# SIRA.net
KiCad netlist of a schematic drawn in Altium Designer
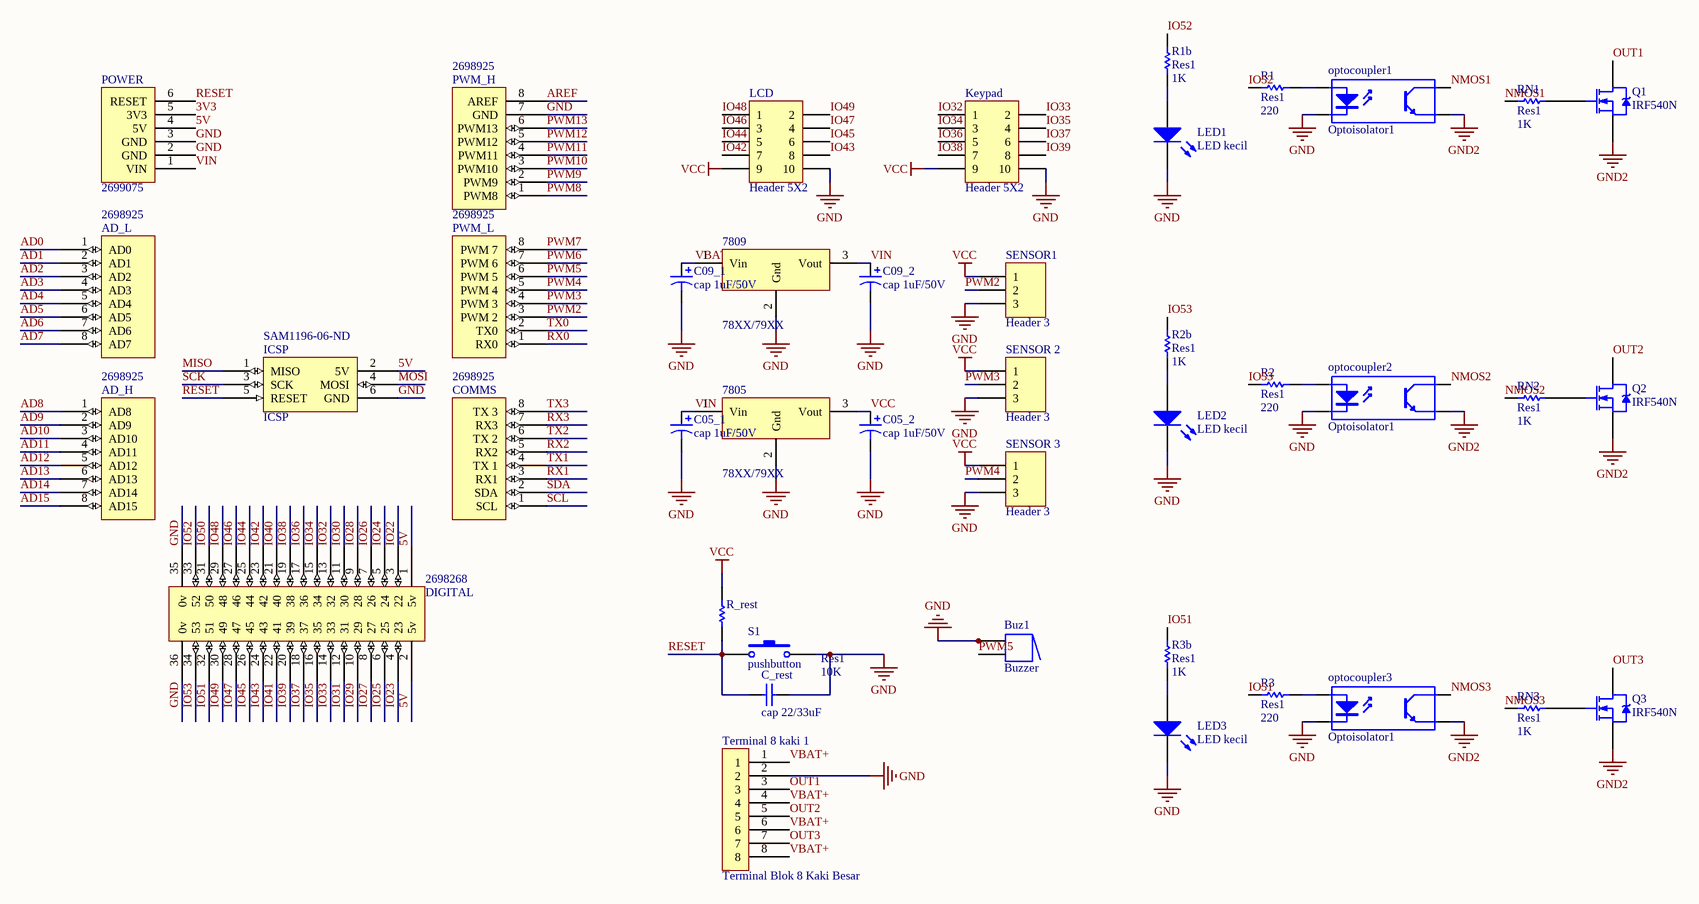
[diagram p0: SIRA.SchDoc]

(export (version "E")
  (design (tool "Eeschema 10.0.6"))
  (components
    (comp (ref "7805")
      (value "78XX/79XX")
      (footprint "78XX/79XX diri")
      (libsource (lib "agfa other components") (part "7805/7809/7812/7905/7909/7912"))
    )
    (comp (ref "7809")
      (value "78XX/79XX")
      (footprint "78XX/79XX diri")
      (libsource (lib "agfa other components") (part "7805/7809/7812/7905/7909/7912"))
    )
    (comp (ref "AD_H")
      (value "AD_H")
      (footprint "Header 8x1 8.5mm")
      (fields (field (name "SUPPLIER PART NUMBER 4") "2698925"))
      (libsource (lib "Header") (part "AD_H"))
    )
    (comp (ref "AD_L")
      (value "AD_L")
      (footprint "Header 8x1 8.5mm")
      (fields (field (name "SUPPLIER PART NUMBER 5") "2698925"))
      (libsource (lib "Header") (part "AD_L"))
    )
    (comp (ref "Buz1")
      (value "Buzzer")
      (footprint "ABSM-1574")
      (description "Magnetic Transducer Buzzer")
      (fields (field (name "PUBLISHER") "Altium Limited"))
      (libsource (lib "Miscellaneous Devices") (part "Buzzer"))
    )
    (comp (ref "C05_1")
      (value "cap 1uF/50V")
      (footprint "cap 1uF/50V")
      (libsource (lib "agfa other components") (part "cap 1uF/50V"))
    )
    (comp (ref "C05_2")
      (value "cap 1uF/50V")
      (footprint "cap 1uF/50V")
      (libsource (lib "agfa other components") (part "cap 1uF/50V"))
    )
    (comp (ref "C09_1")
      (value "cap 1uF/50V")
      (footprint "cap 1uF/50V")
      (libsource (lib "agfa other components") (part "cap 1uF/50V"))
    )
    (comp (ref "C09_2")
      (value "cap 1uF/50V")
      (footprint "cap 1uF/50V")
      (libsource (lib "agfa other components") (part "cap 1uF/50V"))
    )
    (comp (ref "COMMS")
      (value "Communication")
      (footprint "Header 8x1 8.5mm")
      (fields (field (name "SUPPLIER PART NUMBER 4") "2698925"))
      (libsource (lib "Header") (part "Communication"))
    )
    (comp (ref "C_rest")
      (value "cap 22/33uF")
      (footprint "cap 22/33uF")
      (libsource (lib "agfa other components") (part "cap 22/33uF"))
    )
    (comp (ref "DIGITAL")
      (value "IO_36")
      (footprint "HEADER 36X 8MM")
      (fields (field (name "SUPPLIER PART NUMBER 5") "2698268"))
      (libsource (lib "Header") (part "IO_36"))
    )
    (comp (ref "ICSP")
      (value "ICSP")
      (footprint "ICSP")
      (fields (field (name "SUPPLIER PART NUMBER 5") "SAM1196-06-ND"))
      (libsource (lib "Header") (part "ICSP"))
    )
    (comp (ref "Keypad")
      (value "Header 5X2")
      (footprint "HDR2X5")
      (description "Header, 5-Pin, Dual row")
      (fields (field (name "PUBLISHER") "Altium Limited"))
      (libsource (lib "Miscellaneous Connectors") (part "Header 5X2"))
    )
    (comp (ref "LCD")
      (value "Header 5X2")
      (footprint "HDR2X5")
      (description "Header, 5-Pin, Dual row")
      (fields (field (name "PUBLISHER") "Altium Limited"))
      (libsource (lib "Miscellaneous Connectors") (part "Header 5X2"))
    )
    (comp (ref "LED1")
      (value "LED kecil")
      (footprint "LED kecil")
      (libsource (lib "agfa other components") (part "LED kecil"))
    )
    (comp (ref "LED2")
      (value "LED kecil")
      (footprint "LED kecil")
      (libsource (lib "agfa other components") (part "LED kecil"))
    )
    (comp (ref "LED3")
      (value "LED kecil")
      (footprint "LED kecil")
      (libsource (lib "agfa other components") (part "LED kecil"))
    )
    (comp (ref "optocoupler1")
      (value "Optoisolator1")
      (footprint "DIP-4")
      (description "4-Pin Phototransistor Optocoupler")
      (fields (field (name "PUBLISHER") "Altium Limited"))
      (libsource (lib "Miscellaneous Devices") (part "Optoisolator1"))
    )
    (comp (ref "optocoupler2")
      (value "Optoisolator1")
      (footprint "DIP-4")
      (description "4-Pin Phototransistor Optocoupler")
      (fields (field (name "PUBLISHER") "Altium Limited"))
      (libsource (lib "Miscellaneous Devices") (part "Optoisolator1"))
    )
    (comp (ref "optocoupler3")
      (value "Optoisolator1")
      (footprint "DIP-4")
      (description "4-Pin Phototransistor Optocoupler")
      (fields (field (name "PUBLISHER") "Altium Limited"))
      (libsource (lib "Miscellaneous Devices") (part "Optoisolator1"))
    )
    (comp (ref "POWER")
      (value "POWER")
      (footprint "Header 6x1 8.5mm")
      (fields (field (name "SUPPLIER PART NUMBER 2") "2699075"))
      (libsource (lib "Header") (part "POWER"))
    )
    (comp (ref "PWM_H")
      (value "PWM_H")
      (footprint "Header 8x1 8.5mm")
      (fields (field (name "SUPPLIER PART NUMBER 4") "2698925"))
      (libsource (lib "Header") (part "PWM_H"))
    )
    (comp (ref "PWM_L")
      (value "PWM_L")
      (footprint "Header 8x1 8.5mm")
      (fields (field (name "SUPPLIER PART NUMBER 4") "2698925"))
      (libsource (lib "Header") (part "PWM_L"))
    )
    (comp (ref "Q1")
      (value "IRF540N")
      (footprint "TO-220AB")
      (description "HEXFET Power MOSFET")
      (fields (field (name "PUBLISHER") "Altium Limited"))
      (libsource (lib "IR Discrete MOSFET - Power") (part "IRF540N"))
    )
    (comp (ref "Q2")
      (value "IRF540N")
      (footprint "TO-220AB")
      (description "HEXFET Power MOSFET")
      (fields (field (name "PUBLISHER") "Altium Limited"))
      (libsource (lib "IR Discrete MOSFET - Power") (part "IRF540N"))
    )
    (comp (ref "Q3")
      (value "IRF540N")
      (footprint "TO-220AB")
      (description "HEXFET Power MOSFET")
      (fields (field (name "PUBLISHER") "Altium Limited"))
      (libsource (lib "IR Discrete MOSFET - Power") (part "IRF540N"))
    )
    (comp (ref "R1")
      (value "Res1")
      (footprint "AXIAL-0.3")
      (description "Resistor")
      (fields (field (name "ALTIUM_VALUE") "220") (field (name "PUBLISHER") "Altium Limited"))
      (libsource (lib "Miscellaneous Devices") (part "Res1"))
    )
    (comp (ref "R1b")
      (value "Res1")
      (footprint "AXIAL-0.3")
      (description "Resistor")
      (fields (field (name "ALTIUM_VALUE") "1K") (field (name "PUBLISHER") "Altium Limited"))
      (libsource (lib "Miscellaneous Devices") (part "Res1"))
    )
    (comp (ref "R2")
      (value "Res1")
      (footprint "AXIAL-0.3")
      (description "Resistor")
      (fields (field (name "ALTIUM_VALUE") "220") (field (name "PUBLISHER") "Altium Limited"))
      (libsource (lib "Miscellaneous Devices") (part "Res1"))
    )
    (comp (ref "R2b")
      (value "Res1")
      (footprint "AXIAL-0.3")
      (description "Resistor")
      (fields (field (name "ALTIUM_VALUE") "1K") (field (name "PUBLISHER") "Altium Limited"))
      (libsource (lib "Miscellaneous Devices") (part "Res1"))
    )
    (comp (ref "R3")
      (value "Res1")
      (footprint "AXIAL-0.3")
      (description "Resistor")
      (fields (field (name "ALTIUM_VALUE") "220") (field (name "PUBLISHER") "Altium Limited"))
      (libsource (lib "Miscellaneous Devices") (part "Res1"))
    )
    (comp (ref "R3b")
      (value "Res1")
      (footprint "AXIAL-0.3")
      (description "Resistor")
      (fields (field (name "ALTIUM_VALUE") "1K") (field (name "PUBLISHER") "Altium Limited"))
      (libsource (lib "Miscellaneous Devices") (part "Res1"))
    )
    (comp (ref "RN1")
      (value "Res1")
      (footprint "AXIAL-0.3")
      (description "Resistor")
      (fields (field (name "ALTIUM_VALUE") "1K") (field (name "PUBLISHER") "Altium Limited"))
      (libsource (lib "Miscellaneous Devices") (part "Res1"))
    )
    (comp (ref "RN2")
      (value "Res1")
      (footprint "AXIAL-0.3")
      (description "Resistor")
      (fields (field (name "ALTIUM_VALUE") "1K") (field (name "PUBLISHER") "Altium Limited"))
      (libsource (lib "Miscellaneous Devices") (part "Res1"))
    )
    (comp (ref "RN3")
      (value "Res1")
      (footprint "AXIAL-0.3")
      (description "Resistor")
      (fields (field (name "ALTIUM_VALUE") "1K") (field (name "PUBLISHER") "Altium Limited"))
      (libsource (lib "Miscellaneous Devices") (part "Res1"))
    )
    (comp (ref "R_rest")
      (value "Res1")
      (footprint "AXIAL-0.3")
      (description "Resistor")
      (fields (field (name "ALTIUM_VALUE") "10K") (field (name "PUBLISHER") "Altium Limited"))
      (libsource (lib "Miscellaneous Devices") (part "Res1"))
    )
    (comp (ref "S1")
      (value "pushbutton")
      (footprint "pushbutton")
      (libsource (lib "agfa other components") (part "pushbutton"))
    )
    (comp (ref "SENSOR 2")
      (value "Header 3")
      (footprint "HDR1X3")
      (description "Header, 3-Pin")
      (fields (field (name "PUBLISHER") "Altium Limited"))
      (libsource (lib "Miscellaneous Connectors") (part "Header 3"))
    )
    (comp (ref "SENSOR 3")
      (value "Header 3")
      (footprint "HDR1X3")
      (description "Header, 3-Pin")
      (fields (field (name "PUBLISHER") "Altium Limited"))
      (libsource (lib "Miscellaneous Connectors") (part "Header 3"))
    )
    (comp (ref "SENSOR1")
      (value "Header 3")
      (footprint "HDR1X3")
      (description "Header, 3-Pin")
      (fields (field (name "PUBLISHER") "Altium Limited"))
      (libsource (lib "Miscellaneous Connectors") (part "Header 3"))
    )
    (comp (ref "Terminal 8 kaki 1")
      (value "Terminal Blok 8 Kaki Besar")
      (footprint "TERMINAL 8 KAKI")
      (libsource (lib "Library Ausiher") (part "Terminal Block 8 kaki"))
    )
  )
  (nets
    (net (code "1") (name "/3V3") (class "Default")
      (node (ref "POWER") (pin "5") (pinfunction "3V3_5") (pintype "power_in"))
    )
    (net (code "2") (name "/5V") (class "Default")
      (node (ref "DIGITAL") (pin "1") (pinfunction "5v_1") (pintype "power_in"))
      (node (ref "DIGITAL") (pin "2") (pinfunction "5v_2") (pintype "power_in"))
      (node (ref "ICSP") (pin "2") (pinfunction "5V_2") (pintype "power_in"))
      (node (ref "POWER") (pin "4") (pinfunction "5V_4") (pintype "power_in"))
    )
    (net (code "3") (name "/AD0") (class "Default")
      (node (ref "AD_L") (pin "1") (pinfunction "AD0_1") (pintype "bidirectional"))
    )
    (net (code "4") (name "/AD1") (class "Default")
      (node (ref "AD_L") (pin "2") (pinfunction "AD1_2") (pintype "bidirectional"))
    )
    (net (code "5") (name "/AD2") (class "Default")
      (node (ref "AD_L") (pin "3") (pinfunction "AD2_3") (pintype "bidirectional"))
    )
    (net (code "6") (name "/AD3") (class "Default")
      (node (ref "AD_L") (pin "4") (pinfunction "AD3_4") (pintype "bidirectional"))
    )
    (net (code "7") (name "/AD4") (class "Default")
      (node (ref "AD_L") (pin "5") (pinfunction "AD4_5") (pintype "bidirectional"))
    )
    (net (code "8") (name "/AD5") (class "Default")
      (node (ref "AD_L") (pin "6") (pinfunction "AD5_6") (pintype "bidirectional"))
    )
    (net (code "9") (name "/AD6") (class "Default")
      (node (ref "AD_L") (pin "7") (pinfunction "AD6_7") (pintype "bidirectional"))
    )
    (net (code "10") (name "/AD7") (class "Default")
      (node (ref "AD_L") (pin "8") (pinfunction "AD7_8") (pintype "bidirectional"))
    )
    (net (code "11") (name "/AD8") (class "Default")
      (node (ref "AD_H") (pin "1") (pinfunction "AD8_1") (pintype "bidirectional"))
    )
    (net (code "12") (name "/AD9") (class "Default")
      (node (ref "AD_H") (pin "2") (pinfunction "AD9_2") (pintype "bidirectional"))
    )
    (net (code "13") (name "/AD10") (class "Default")
      (node (ref "AD_H") (pin "3") (pinfunction "AD10_3") (pintype "bidirectional"))
    )
    (net (code "14") (name "/AD11") (class "Default")
      (node (ref "AD_H") (pin "4") (pinfunction "AD11_4") (pintype "bidirectional"))
    )
    (net (code "15") (name "/AD12") (class "Default")
      (node (ref "AD_H") (pin "5") (pinfunction "AD12_5") (pintype "bidirectional"))
    )
    (net (code "16") (name "/AD13") (class "Default")
      (node (ref "AD_H") (pin "6") (pinfunction "AD13_6") (pintype "bidirectional"))
    )
    (net (code "17") (name "/AD14") (class "Default")
      (node (ref "AD_H") (pin "7") (pinfunction "AD14_7") (pintype "bidirectional"))
    )
    (net (code "18") (name "/AD15") (class "Default")
      (node (ref "AD_H") (pin "8") (pinfunction "AD15_8") (pintype "bidirectional"))
    )
    (net (code "19") (name "/AREF") (class "Default")
      (node (ref "PWM_H") (pin "8") (pinfunction "AREF_8") (pintype "passive"))
    )
    (net (code "20") (name "/IO22") (class "Default")
      (node (ref "DIGITAL") (pin "3") (pinfunction "22_3") (pintype "bidirectional"))
    )
    (net (code "21") (name "/IO23") (class "Default")
      (node (ref "DIGITAL") (pin "4") (pinfunction "23_4") (pintype "bidirectional"))
    )
    (net (code "22") (name "/IO24") (class "Default")
      (node (ref "DIGITAL") (pin "5") (pinfunction "24_5") (pintype "bidirectional"))
    )
    (net (code "23") (name "/IO25") (class "Default")
      (node (ref "DIGITAL") (pin "6") (pinfunction "25_6") (pintype "bidirectional"))
    )
    (net (code "24") (name "/IO26") (class "Default")
      (node (ref "DIGITAL") (pin "7") (pinfunction "26_7") (pintype "bidirectional"))
    )
    (net (code "25") (name "/IO27") (class "Default")
      (node (ref "DIGITAL") (pin "8") (pinfunction "27_8") (pintype "bidirectional"))
    )
    (net (code "26") (name "/IO28") (class "Default")
      (node (ref "DIGITAL") (pin "9") (pinfunction "28_9") (pintype "bidirectional"))
    )
    (net (code "27") (name "/IO29") (class "Default")
      (node (ref "DIGITAL") (pin "10") (pinfunction "29_10") (pintype "bidirectional"))
    )
    (net (code "28") (name "/IO30") (class "Default")
      (node (ref "DIGITAL") (pin "11") (pinfunction "30_11") (pintype "bidirectional"))
    )
    (net (code "29") (name "/IO31") (class "Default")
      (node (ref "DIGITAL") (pin "12") (pinfunction "31_12") (pintype "bidirectional"))
    )
    (net (code "30") (name "/IO32") (class "Default")
      (node (ref "DIGITAL") (pin "13") (pinfunction "32_13") (pintype "bidirectional"))
      (node (ref "Keypad") (pin "1") (pinfunction "1_1") (pintype "passive"))
    )
    (net (code "31") (name "/IO33") (class "Default")
      (node (ref "DIGITAL") (pin "14") (pinfunction "33_14") (pintype "bidirectional"))
      (node (ref "Keypad") (pin "2") (pinfunction "2_2") (pintype "passive"))
    )
    (net (code "32") (name "/IO34") (class "Default")
      (node (ref "DIGITAL") (pin "15") (pinfunction "34_15") (pintype "bidirectional"))
      (node (ref "Keypad") (pin "3") (pinfunction "3_3") (pintype "passive"))
    )
    (net (code "33") (name "/IO35") (class "Default")
      (node (ref "DIGITAL") (pin "16") (pinfunction "35_16") (pintype "bidirectional"))
      (node (ref "Keypad") (pin "4") (pinfunction "4_4") (pintype "passive"))
    )
    (net (code "34") (name "/IO36") (class "Default")
      (node (ref "DIGITAL") (pin "17") (pinfunction "36_17") (pintype "bidirectional"))
      (node (ref "Keypad") (pin "5") (pinfunction "5_5") (pintype "passive"))
    )
    (net (code "35") (name "/IO37") (class "Default")
      (node (ref "DIGITAL") (pin "18") (pinfunction "37_18") (pintype "bidirectional"))
      (node (ref "Keypad") (pin "6") (pinfunction "6_6") (pintype "passive"))
    )
    (net (code "36") (name "/IO38") (class "Default")
      (node (ref "DIGITAL") (pin "19") (pinfunction "38_19") (pintype "bidirectional"))
      (node (ref "Keypad") (pin "7") (pinfunction "7_7") (pintype "passive"))
    )
    (net (code "37") (name "/IO39") (class "Default")
      (node (ref "DIGITAL") (pin "20") (pinfunction "39_20") (pintype "bidirectional"))
      (node (ref "Keypad") (pin "8") (pinfunction "8_8") (pintype "passive"))
    )
    (net (code "38") (name "/IO40") (class "Default")
      (node (ref "DIGITAL") (pin "21") (pinfunction "40_21") (pintype "bidirectional"))
    )
    (net (code "39") (name "/IO41") (class "Default")
      (node (ref "DIGITAL") (pin "22") (pinfunction "41_22") (pintype "bidirectional"))
    )
    (net (code "40") (name "/IO42") (class "Default")
      (node (ref "DIGITAL") (pin "23") (pinfunction "42_23") (pintype "bidirectional"))
      (node (ref "LCD") (pin "7") (pinfunction "7_7") (pintype "passive"))
    )
    (net (code "41") (name "/IO43") (class "Default")
      (node (ref "DIGITAL") (pin "24") (pinfunction "43_24") (pintype "bidirectional"))
      (node (ref "LCD") (pin "8") (pinfunction "8_8") (pintype "passive"))
    )
    (net (code "42") (name "/IO44") (class "Default")
      (node (ref "DIGITAL") (pin "25") (pinfunction "44_25") (pintype "bidirectional"))
      (node (ref "LCD") (pin "5") (pinfunction "5_5") (pintype "passive"))
    )
    (net (code "43") (name "/IO45") (class "Default")
      (node (ref "DIGITAL") (pin "26") (pinfunction "45_26") (pintype "bidirectional"))
      (node (ref "LCD") (pin "6") (pinfunction "6_6") (pintype "passive"))
    )
    (net (code "44") (name "/IO46") (class "Default")
      (node (ref "DIGITAL") (pin "27") (pinfunction "46_27") (pintype "bidirectional"))
      (node (ref "LCD") (pin "3") (pinfunction "3_3") (pintype "passive"))
    )
    (net (code "45") (name "/IO47") (class "Default")
      (node (ref "DIGITAL") (pin "28") (pinfunction "47_28") (pintype "bidirectional"))
      (node (ref "LCD") (pin "4") (pinfunction "4_4") (pintype "passive"))
    )
    (net (code "46") (name "/IO48") (class "Default")
      (node (ref "DIGITAL") (pin "29") (pinfunction "48_29") (pintype "bidirectional"))
      (node (ref "LCD") (pin "1") (pinfunction "1_1") (pintype "passive"))
    )
    (net (code "47") (name "/IO49") (class "Default")
      (node (ref "DIGITAL") (pin "30") (pinfunction "49_30") (pintype "bidirectional"))
      (node (ref "LCD") (pin "2") (pinfunction "2_2") (pintype "passive"))
    )
    (net (code "48") (name "/IO50") (class "Default")
      (node (ref "DIGITAL") (pin "31") (pinfunction "50_31") (pintype "bidirectional"))
    )
    (net (code "49") (name "/IO51") (class "Default")
      (node (ref "DIGITAL") (pin "32") (pinfunction "51_32") (pintype "bidirectional"))
      (node (ref "R3") (pin "1") (pinfunction "1_1") (pintype "passive"))
      (node (ref "R3b") (pin "2") (pinfunction "2_2") (pintype "passive"))
    )
    (net (code "50") (name "/IO52") (class "Default")
      (node (ref "DIGITAL") (pin "33") (pinfunction "52_33") (pintype "bidirectional"))
      (node (ref "R1") (pin "1") (pinfunction "1_1") (pintype "passive"))
      (node (ref "R1b") (pin "2") (pinfunction "2_2") (pintype "passive"))
    )
    (net (code "51") (name "/IO53") (class "Default")
      (node (ref "DIGITAL") (pin "34") (pinfunction "53_34") (pintype "bidirectional"))
      (node (ref "R2") (pin "1") (pinfunction "1_1") (pintype "passive"))
      (node (ref "R2b") (pin "2") (pinfunction "2_2") (pintype "passive"))
    )
    (net (code "52") (name "/MISO") (class "Default")
      (node (ref "ICSP") (pin "1") (pinfunction "MISO_1") (pintype "bidirectional"))
    )
    (net (code "53") (name "/MOSI") (class "Default")
      (node (ref "ICSP") (pin "4") (pinfunction "MOSI_4") (pintype "bidirectional"))
    )
    (net (code "54") (name "/NMOS1") (class "Default")
      (node (ref "RN1") (pin "1") (pinfunction "1_1") (pintype "passive"))
      (node (ref "optocoupler1") (pin "4") (pinfunction "C_4") (pintype "passive"))
    )
    (net (code "55") (name "/NMOS2") (class "Default")
      (node (ref "RN2") (pin "1") (pinfunction "1_1") (pintype "passive"))
      (node (ref "optocoupler2") (pin "4") (pinfunction "C_4") (pintype "passive"))
    )
    (net (code "56") (name "/NMOS3") (class "Default")
      (node (ref "RN3") (pin "1") (pinfunction "1_1") (pintype "passive"))
      (node (ref "optocoupler3") (pin "4") (pinfunction "C_4") (pintype "passive"))
    )
    (net (code "57") (name "/OUT1") (class "Default")
      (node (ref "Q1") (pin "2") (pinfunction "D_2") (pintype "passive"))
      (node (ref "Terminal 8 kaki 1") (pin "3") (pinfunction "3_3") (pintype "passive"))
    )
    (net (code "58") (name "/OUT2") (class "Default")
      (node (ref "Q2") (pin "2") (pinfunction "D_2") (pintype "passive"))
      (node (ref "Terminal 8 kaki 1") (pin "5") (pinfunction "5_5") (pintype "passive"))
    )
    (net (code "59") (name "/OUT3") (class "Default")
      (node (ref "Q3") (pin "2") (pinfunction "D_2") (pintype "passive"))
      (node (ref "Terminal 8 kaki 1") (pin "7") (pinfunction "7_7") (pintype "passive"))
    )
    (net (code "60") (name "/PWM2") (class "Default")
      (node (ref "PWM_L") (pin "3") (pinfunction "PWM_2_3") (pintype "bidirectional"))
      (node (ref "SENSOR1") (pin "2") (pinfunction "2_2") (pintype "passive"))
    )
    (net (code "61") (name "/PWM3") (class "Default")
      (node (ref "PWM_L") (pin "4") (pinfunction "PWM_3_4") (pintype "bidirectional"))
      (node (ref "SENSOR 2") (pin "2") (pinfunction "2_2") (pintype "passive"))
    )
    (net (code "62") (name "/PWM4") (class "Default")
      (node (ref "PWM_L") (pin "5") (pinfunction "PWM_4_5") (pintype "bidirectional"))
      (node (ref "SENSOR 3") (pin "2") (pinfunction "2_2") (pintype "passive"))
    )
    (net (code "63") (name "/PWM5") (class "Default")
      (node (ref "Buz1") (pin "2") (pinfunction "2_2") (pintype "passive"))
      (node (ref "Buz1") (pin "2A") (pinfunction "2A_2A") (pintype "passive"))
      (node (ref "PWM_L") (pin "6") (pinfunction "PWM_5_6") (pintype "bidirectional"))
    )
    (net (code "64") (name "/PWM6") (class "Default")
      (node (ref "PWM_L") (pin "7") (pinfunction "PWM_6_7") (pintype "bidirectional"))
    )
    (net (code "65") (name "/PWM7") (class "Default")
      (node (ref "PWM_L") (pin "8") (pinfunction "PWM_7_8") (pintype "bidirectional"))
    )
    (net (code "66") (name "/PWM8") (class "Default")
      (node (ref "PWM_H") (pin "1") (pinfunction "PWM8_1") (pintype "bidirectional"))
    )
    (net (code "67") (name "/PWM9") (class "Default")
      (node (ref "PWM_H") (pin "2") (pinfunction "PWM9_2") (pintype "bidirectional"))
    )
    (net (code "68") (name "/PWM10") (class "Default")
      (node (ref "PWM_H") (pin "3") (pinfunction "PWM10_3") (pintype "bidirectional"))
    )
    (net (code "69") (name "/PWM11") (class "Default")
      (node (ref "PWM_H") (pin "4") (pinfunction "PWM11_4") (pintype "bidirectional"))
    )
    (net (code "70") (name "/PWM12") (class "Default")
      (node (ref "PWM_H") (pin "5") (pinfunction "PWM12_5") (pintype "bidirectional"))
    )
    (net (code "71") (name "/PWM13") (class "Default")
      (node (ref "PWM_H") (pin "6") (pinfunction "PWM13_6") (pintype "bidirectional"))
    )
    (net (code "72") (name "/RESET") (class "Default")
      (node (ref "C_rest") (pin "2") (pinfunction "2_2") (pintype "passive"))
      (node (ref "ICSP") (pin "5") (pinfunction "RESET_5") (pintype "input"))
      (node (ref "POWER") (pin "6") (pinfunction "RESET_6") (pintype "passive"))
      (node (ref "R_rest") (pin "1") (pinfunction "1_1") (pintype "passive"))
      (node (ref "S1") (pin "1") (pinfunction "1_1") (pintype "passive"))
    )
    (net (code "73") (name "/RX0") (class "Default")
      (node (ref "PWM_L") (pin "1") (pinfunction "RX0_1") (pintype "bidirectional"))
    )
    (net (code "74") (name "/RX1") (class "Default")
      (node (ref "COMMS") (pin "3") (pinfunction "RX1_3") (pintype "bidirectional"))
    )
    (net (code "75") (name "/RX2") (class "Default")
      (node (ref "COMMS") (pin "5") (pinfunction "RX2_5") (pintype "bidirectional"))
    )
    (net (code "76") (name "/RX3") (class "Default")
      (node (ref "COMMS") (pin "7") (pinfunction "RX3_7") (pintype "bidirectional"))
    )
    (net (code "77") (name "/SCK") (class "Default")
      (node (ref "ICSP") (pin "3") (pinfunction "SCK_3") (pintype "bidirectional"))
    )
    (net (code "78") (name "/SCL") (class "Default")
      (node (ref "COMMS") (pin "1") (pinfunction "SCL_1") (pintype "bidirectional"))
    )
    (net (code "79") (name "/SDA") (class "Default")
      (node (ref "COMMS") (pin "2") (pinfunction "SDA_2") (pintype "bidirectional"))
    )
    (net (code "80") (name "/TX0") (class "Default")
      (node (ref "PWM_L") (pin "2") (pinfunction "TX0_2") (pintype "bidirectional"))
    )
    (net (code "81") (name "/TX1") (class "Default")
      (node (ref "COMMS") (pin "4") (pinfunction "TX_1_4") (pintype "bidirectional"))
    )
    (net (code "82") (name "/TX2") (class "Default")
      (node (ref "COMMS") (pin "6") (pinfunction "TX_2_6") (pintype "bidirectional"))
    )
    (net (code "83") (name "/TX3") (class "Default")
      (node (ref "COMMS") (pin "8") (pinfunction "TX_3_8") (pintype "bidirectional"))
    )
    (net (code "84") (name "/VBAT+") (class "Default")
      (node (ref "7809") (pin "1") (pinfunction "Vin_1") (pintype "passive"))
      (node (ref "C09_1") (pin "1") (pinfunction "1_1") (pintype "passive"))
      (node (ref "Terminal 8 kaki 1") (pin "1") (pinfunction "1_1") (pintype "passive"))
      (node (ref "Terminal 8 kaki 1") (pin "4") (pinfunction "4_4") (pintype "passive"))
      (node (ref "Terminal 8 kaki 1") (pin "6") (pinfunction "6_6") (pintype "passive"))
      (node (ref "Terminal 8 kaki 1") (pin "8") (pinfunction "8_8") (pintype "passive"))
    )
    (net (code "85") (name "/VIN") (class "Default")
      (node (ref "7805") (pin "1") (pinfunction "Vin_1") (pintype "passive"))
      (node (ref "7809") (pin "3") (pinfunction "Vout_3") (pintype "passive"))
      (node (ref "C05_1") (pin "1") (pinfunction "1_1") (pintype "passive"))
      (node (ref "C09_2") (pin "1") (pinfunction "1_1") (pintype "passive"))
      (node (ref "POWER") (pin "1") (pinfunction "VIN_1") (pintype "power_in"))
    )
    (net (code "86") (name "GND") (class "Default")
      (node (ref "7805") (pin "2") (pinfunction "Gnd_2") (pintype "passive"))
      (node (ref "7809") (pin "2") (pinfunction "Gnd_2") (pintype "passive"))
      (node (ref "Buz1") (pin "1") (pinfunction "1_1") (pintype "passive"))
      (node (ref "Buz1") (pin "1A") (pinfunction "1A_1A") (pintype "passive"))
      (node (ref "C05_1") (pin "2") (pinfunction "2_2") (pintype "passive"))
      (node (ref "C05_2") (pin "2") (pinfunction "2_2") (pintype "passive"))
      (node (ref "C09_1") (pin "2") (pinfunction "2_2") (pintype "passive"))
      (node (ref "C09_2") (pin "2") (pinfunction "2_2") (pintype "passive"))
      (node (ref "C_rest") (pin "1") (pinfunction "1_1") (pintype "passive"))
      (node (ref "DIGITAL") (pin "35") (pinfunction "0v_35") (pintype "power_in"))
      (node (ref "DIGITAL") (pin "36") (pinfunction "0v_36") (pintype "power_in"))
      (node (ref "ICSP") (pin "6") (pinfunction "GND_6") (pintype "power_in"))
      (node (ref "Keypad") (pin "10") (pinfunction "10_10") (pintype "passive"))
      (node (ref "LCD") (pin "10") (pinfunction "10_10") (pintype "passive"))
      (node (ref "LED1") (pin "2") (pinfunction "K_2") (pintype "passive"))
      (node (ref "LED2") (pin "2") (pinfunction "K_2") (pintype "passive"))
      (node (ref "LED3") (pin "2") (pinfunction "K_2") (pintype "passive"))
      (node (ref "POWER") (pin "2") (pinfunction "GND_2") (pintype "power_in"))
      (node (ref "POWER") (pin "3") (pinfunction "GND_3") (pintype "power_in"))
      (node (ref "PWM_H") (pin "7") (pinfunction "GND_7") (pintype "power_in"))
      (node (ref "S1") (pin "2") (pinfunction "2_2") (pintype "passive"))
      (node (ref "SENSOR 2") (pin "3") (pinfunction "3_3") (pintype "passive"))
      (node (ref "SENSOR 3") (pin "3") (pinfunction "3_3") (pintype "passive"))
      (node (ref "SENSOR1") (pin "3") (pinfunction "3_3") (pintype "passive"))
      (node (ref "Terminal 8 kaki 1") (pin "2") (pinfunction "2_2") (pintype "passive"))
      (node (ref "optocoupler1") (pin "2") (pinfunction "K_2") (pintype "passive"))
      (node (ref "optocoupler2") (pin "2") (pinfunction "K_2") (pintype "passive"))
      (node (ref "optocoupler3") (pin "2") (pinfunction "K_2") (pintype "passive"))
    )
    (net (code "87") (name "GND2") (class "Default")
      (node (ref "Q1") (pin "3") (pinfunction "S_3") (pintype "passive"))
      (node (ref "Q2") (pin "3") (pinfunction "S_3") (pintype "passive"))
      (node (ref "Q3") (pin "3") (pinfunction "S_3") (pintype "passive"))
      (node (ref "optocoupler1") (pin "3") (pinfunction "E_3") (pintype "passive"))
      (node (ref "optocoupler2") (pin "3") (pinfunction "E_3") (pintype "passive"))
      (node (ref "optocoupler3") (pin "3") (pinfunction "E_3") (pintype "passive"))
    )
    (net (code "88") (name "Net-(LED1-A)") (class "Default")
      (node (ref "LED1") (pin "1") (pinfunction "A_1") (pintype "passive"))
      (node (ref "R1b") (pin "1") (pinfunction "1_1") (pintype "passive"))
    )
    (net (code "89") (name "Net-(LED2-A)") (class "Default")
      (node (ref "LED2") (pin "1") (pinfunction "A_1") (pintype "passive"))
      (node (ref "R2b") (pin "1") (pinfunction "1_1") (pintype "passive"))
    )
    (net (code "90") (name "Net-(LED3-A)") (class "Default")
      (node (ref "LED3") (pin "1") (pinfunction "A_1") (pintype "passive"))
      (node (ref "R3b") (pin "1") (pinfunction "1_1") (pintype "passive"))
    )
    (net (code "91") (name "Net-(Q1-G)") (class "Default")
      (node (ref "Q1") (pin "1") (pinfunction "G_1") (pintype "passive"))
      (node (ref "RN1") (pin "2") (pinfunction "2_2") (pintype "passive"))
    )
    (net (code "92") (name "Net-(Q2-G)") (class "Default")
      (node (ref "Q2") (pin "1") (pinfunction "G_1") (pintype "passive"))
      (node (ref "RN2") (pin "2") (pinfunction "2_2") (pintype "passive"))
    )
    (net (code "93") (name "Net-(Q3-G)") (class "Default")
      (node (ref "Q3") (pin "1") (pinfunction "G_1") (pintype "passive"))
      (node (ref "RN3") (pin "2") (pinfunction "2_2") (pintype "passive"))
    )
    (net (code "94") (name "Net-(optocoupler1-A)") (class "Default")
      (node (ref "R1") (pin "2") (pinfunction "2_2") (pintype "passive"))
      (node (ref "optocoupler1") (pin "1") (pinfunction "A_1") (pintype "passive"))
    )
    (net (code "95") (name "Net-(optocoupler2-A)") (class "Default")
      (node (ref "R2") (pin "2") (pinfunction "2_2") (pintype "passive"))
      (node (ref "optocoupler2") (pin "1") (pinfunction "A_1") (pintype "passive"))
    )
    (net (code "96") (name "Net-(optocoupler3-A)") (class "Default")
      (node (ref "R3") (pin "2") (pinfunction "2_2") (pintype "passive"))
      (node (ref "optocoupler3") (pin "1") (pinfunction "A_1") (pintype "passive"))
    )
    (net (code "97") (name "VCC") (class "Default")
      (node (ref "7805") (pin "3") (pinfunction "Vout_3") (pintype "passive"))
      (node (ref "C05_2") (pin "1") (pinfunction "1_1") (pintype "passive"))
      (node (ref "Keypad") (pin "9") (pinfunction "9_9") (pintype "passive"))
      (node (ref "LCD") (pin "9") (pinfunction "9_9") (pintype "passive"))
      (node (ref "R_rest") (pin "2") (pinfunction "2_2") (pintype "passive"))
      (node (ref "SENSOR 2") (pin "1") (pinfunction "1_1") (pintype "passive"))
      (node (ref "SENSOR 3") (pin "1") (pinfunction "1_1") (pintype "passive"))
      (node (ref "SENSOR1") (pin "1") (pinfunction "1_1") (pintype "passive"))
    )
  )
)
